# nanoDAP.net
KiCad netlist of a schematic drawn in Altium Designer
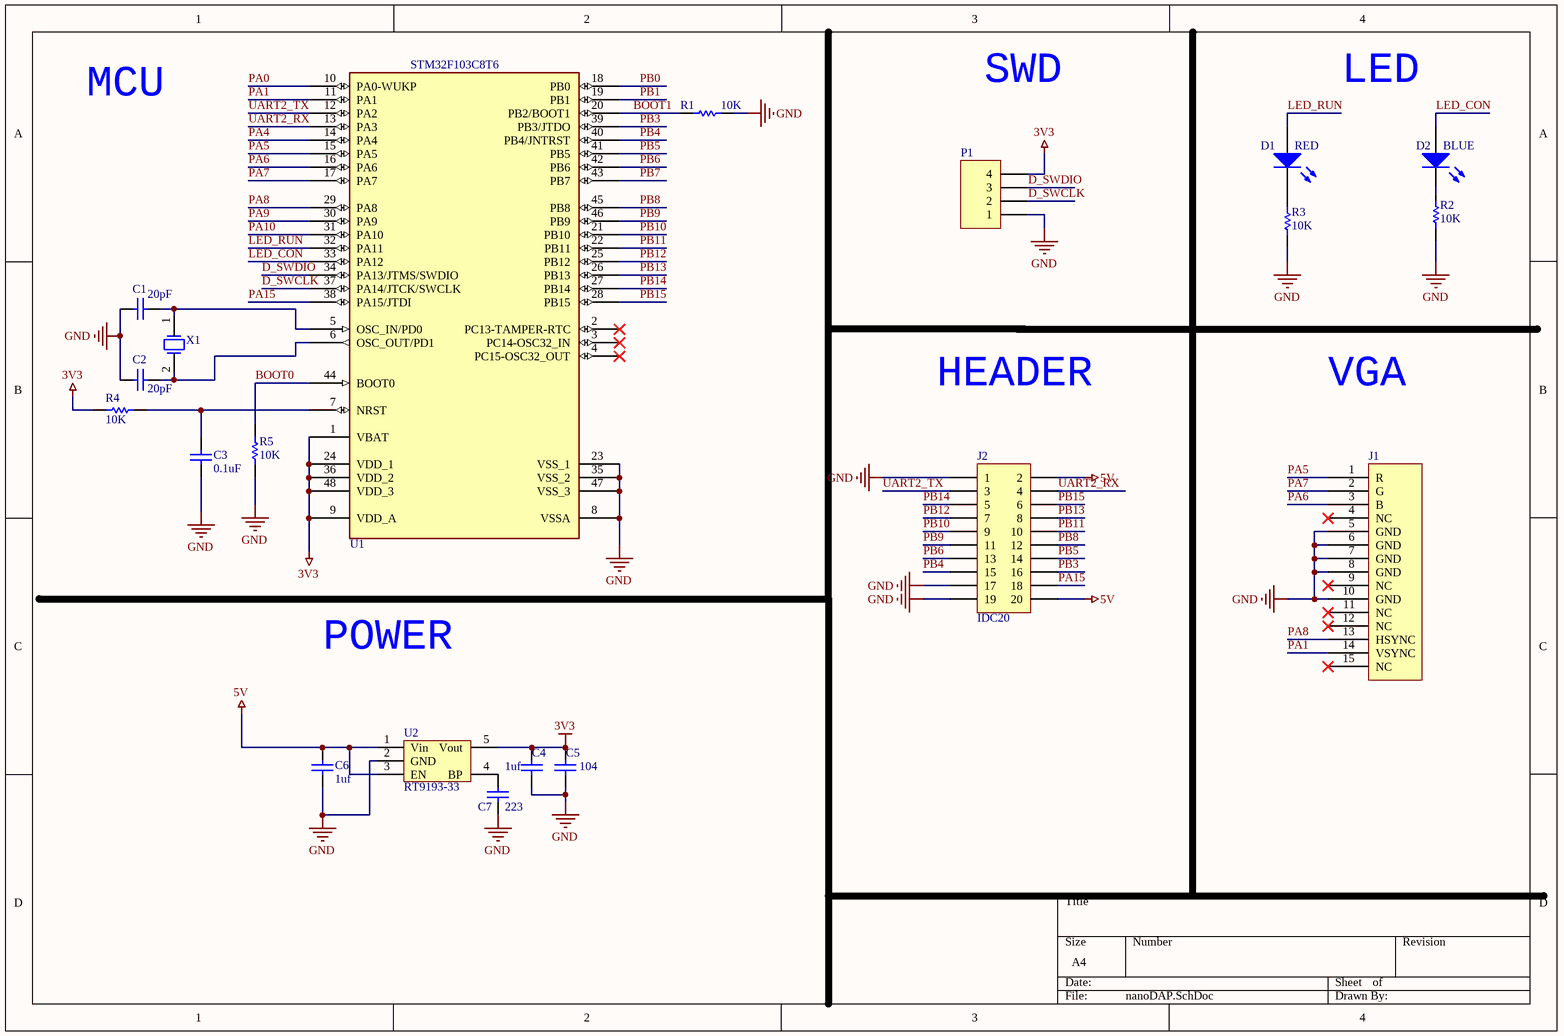
[diagram p0: nanoDAP.SchDoc]

(export (version "E")
  (design (tool "Eeschema 10.0.6"))
  (components
    (comp (ref "C1")
      (value "20pF")
      (footprint "0603_C")
      (description "Capacitor")
      (fields (field (name "Comment") "C0603") (field (name "PUBLISHER") "Altium Limited"))
      (libsource (lib "MYLIB") (part "C-RAD-0603"))
    )
    (comp (ref "C2")
      (value "20pF")
      (footprint "0603_C")
      (description "Capacitor")
      (fields (field (name "Comment") "C0603") (field (name "PUBLISHER") "Altium Limited"))
      (libsource (lib "MYLIB") (part "C-RAD-0603"))
    )
    (comp (ref "C3")
      (value "0.1uF")
      (footprint "0603_C")
      (description "Capacitor")
      (fields (field (name "Comment") "C0603") (field (name "PUBLISHER") "Altium Limited"))
      (libsource (lib "MYLIB") (part "C-RAD-0603"))
    )
    (comp (ref "C4")
      (value "1uf")
      (footprint "0603_C")
      (description "Capacitor")
      (libsource (lib "Cheetie Integrated Library 2017") (part "CAP"))
    )
    (comp (ref "C5")
      (value "104")
      (footprint "0603_C")
      (description "Capacitor")
      (libsource (lib "Cheetie Integrated Library 2017") (part "CAP"))
    )
    (comp (ref "C6")
      (value "1uf")
      (footprint "0603_C")
      (description "Capacitor")
      (libsource (lib "Cheetie Integrated Library 2017") (part "CAP"))
    )
    (comp (ref "C7")
      (value "223")
      (footprint "0603_C")
      (description "Capacitor")
      (libsource (lib "Cheetie Integrated Library 2017") (part "CAP"))
    )
    (comp (ref "D1")
      (value "RED")
      (footprint "0603_LED")
      (description "Typical RED, GREEN, YELLOW, AMBER GaAs LED")
      (fields (field (name "PUBLISHER") "Altium Limited"))
      (libsource (lib "MYLIB") (part "D0603"))
    )
    (comp (ref "D2")
      (value "BLUE")
      (footprint "0603_LED")
      (description "Typical RED, GREEN, YELLOW, AMBER GaAs LED")
      (fields (field (name "PUBLISHER") "Altium Limited"))
      (libsource (lib "MYLIB") (part "D0603"))
    )
    (comp (ref "J1")
      (value "VGA_FEMALE")
      (footprint "VGA15B")
      (libsource (lib "nanoDAP") (part "VGA_FEMALE"))
    )
    (comp (ref "J2") (value "IDC20") (footprint "IDC20") (libsource (lib "nanoDAP") (part "IDC20")))
    (comp (ref "P1")
      (value "Header 4")
      (footprint "HEADER_4x1")
      (description "Header, 4-Pin")
      (fields (field (name "PUBLISHER") "Altium Limited"))
      (libsource (lib "Miscellaneous Connectors") (part "Header 4"))
    )
    (comp (ref "R1")
      (value "10K")
      (footprint "0603_R")
      (description "Resistor")
      (fields (field (name "Comment") "R0603") (field (name "PUBLISHER") "Altium Limited"))
      (libsource (lib "MYLIB") (part "R0603"))
    )
    (comp (ref "R2")
      (value "10K")
      (footprint "0603_R")
      (description "Resistor")
      (fields (field (name "Comment") "R0603") (field (name "PUBLISHER") "Altium Limited"))
      (libsource (lib "MYLIB") (part "0603-1"))
    )
    (comp (ref "R3")
      (value "10K")
      (footprint "0603_R")
      (description "Resistor")
      (fields (field (name "Comment") "R0603") (field (name "PUBLISHER") "Altium Limited"))
      (libsource (lib "MYLIB") (part "0603-1"))
    )
    (comp (ref "R4")
      (value "10K")
      (footprint "0603_R")
      (description "Resistor")
      (fields (field (name "Comment") "R0603") (field (name "PUBLISHER") "Altium Limited"))
      (libsource (lib "MYLIB") (part "0603-1"))
    )
    (comp (ref "R5")
      (value "10K")
      (footprint "0603_R")
      (description "Resistor")
      (fields (field (name "Comment") "R0603") (field (name "PUBLISHER") "Altium Limited"))
      (libsource (lib "MYLIB") (part "0603-1"))
    )
    (comp (ref "U1")
      (value "STM32F103C8T6")
      (footprint "LQFP48_N")
      (description "LowPower MCU")
      (libsource (lib "MYLIB") (part "STM32F103C8T6"))
    )
    (comp (ref "U2")
      (value "RT9193-33")
      (footprint "SOT23-5")
      (libsource (lib "Cheetie Integrated Library 2017") (part "RT9193-33"))
    )
    (comp (ref "X1") (value "XTAL") (footprint "49SMD") (libsource (lib "MYLIB") (part "XTAL")))
  )
  (nets
    (net (code "1") (name "/BOOT0") (class "Default")
      (node (ref "R5") (pin "1") (pinfunction "1_1") (pintype "passive"))
      (node (ref "U1") (pin "44") (pinfunction "BOOT0_44") (pintype "input"))
    )
    (net (code "2") (name "/BOOT1") (class "Default")
      (node (ref "R1") (pin "2") (pinfunction "2_2") (pintype "passive"))
      (node (ref "U1") (pin "20") (pinfunction "PB2/BOOT1_20") (pintype "bidirectional"))
    )
    (net (code "3") (name "/D_SWCLK") (class "Default")
      (node (ref "P1") (pin "2") (pinfunction "2_2") (pintype "passive"))
      (node (ref "U1") (pin "37") (pinfunction "PA14/JTCK/SWCLK_37") (pintype "bidirectional"))
    )
    (net (code "4") (name "/D_SWDIO") (class "Default")
      (node (ref "P1") (pin "3") (pinfunction "3_3") (pintype "passive"))
      (node (ref "U1") (pin "34") (pinfunction "PA13/JTMS/SWDIO_34") (pintype "bidirectional"))
    )
    (net (code "5") (name "/LED_CON") (class "Default")
      (node (ref "D2") (pin "1") (pinfunction "A_1") (pintype "passive"))
      (node (ref "U1") (pin "33") (pinfunction "PA12_33") (pintype "bidirectional"))
    )
    (net (code "6") (name "/LED_RUN") (class "Default")
      (node (ref "D1") (pin "1") (pinfunction "A_1") (pintype "passive"))
      (node (ref "U1") (pin "32") (pinfunction "PA11_32") (pintype "bidirectional"))
    )
    (net (code "7") (name "/PA0") (class "Default")
      (node (ref "U1") (pin "10") (pinfunction "PA0-WUKP_10") (pintype "bidirectional"))
    )
    (net (code "8") (name "/PA1") (class "Default")
      (node (ref "J1") (pin "14") (pinfunction "VSYNC_14") (pintype "passive"))
      (node (ref "U1") (pin "11") (pinfunction "PA1_11") (pintype "bidirectional"))
    )
    (net (code "9") (name "/PA4") (class "Default")
      (node (ref "U1") (pin "14") (pinfunction "PA4_14") (pintype "bidirectional"))
    )
    (net (code "10") (name "/PA5") (class "Default")
      (node (ref "J1") (pin "1") (pinfunction "R_1") (pintype "passive"))
      (node (ref "U1") (pin "15") (pinfunction "PA5_15") (pintype "bidirectional"))
    )
    (net (code "11") (name "/PA6") (class "Default")
      (node (ref "J1") (pin "3") (pinfunction "B_3") (pintype "passive"))
      (node (ref "U1") (pin "16") (pinfunction "PA6_16") (pintype "bidirectional"))
    )
    (net (code "12") (name "/PA7") (class "Default")
      (node (ref "J1") (pin "2") (pinfunction "G_2") (pintype "passive"))
      (node (ref "U1") (pin "17") (pinfunction "PA7_17") (pintype "bidirectional"))
    )
    (net (code "13") (name "/PA8") (class "Default")
      (node (ref "J1") (pin "13") (pinfunction "HSYNC_13") (pintype "passive"))
      (node (ref "U1") (pin "29") (pinfunction "PA8_29") (pintype "bidirectional"))
    )
    (net (code "14") (name "/PA9") (class "Default")
      (node (ref "U1") (pin "30") (pinfunction "PA9_30") (pintype "bidirectional"))
    )
    (net (code "15") (name "/PA10") (class "Default")
      (node (ref "U1") (pin "31") (pinfunction "PA10_31") (pintype "bidirectional"))
    )
    (net (code "16") (name "/PA15") (class "Default")
      (node (ref "J2") (pin "18") (pinfunction "18_18") (pintype "passive"))
      (node (ref "U1") (pin "38") (pinfunction "PA15/JTDI_38") (pintype "bidirectional"))
    )
    (net (code "17") (name "/PB0") (class "Default")
      (node (ref "U1") (pin "18") (pinfunction "PB0_18") (pintype "bidirectional"))
    )
    (net (code "18") (name "/PB1") (class "Default")
      (node (ref "U1") (pin "19") (pinfunction "PB1_19") (pintype "bidirectional"))
    )
    (net (code "19") (name "/PB3") (class "Default")
      (node (ref "J2") (pin "16") (pinfunction "16_16") (pintype "passive"))
      (node (ref "U1") (pin "39") (pinfunction "PB3/JTDO_39") (pintype "bidirectional"))
    )
    (net (code "20") (name "/PB4") (class "Default")
      (node (ref "J2") (pin "15") (pinfunction "15_15") (pintype "passive"))
      (node (ref "U1") (pin "40") (pinfunction "PB4/JNTRST_40") (pintype "bidirectional"))
    )
    (net (code "21") (name "/PB5") (class "Default")
      (node (ref "J2") (pin "14") (pinfunction "14_14") (pintype "passive"))
      (node (ref "U1") (pin "41") (pinfunction "PB5_41") (pintype "bidirectional"))
    )
    (net (code "22") (name "/PB6") (class "Default")
      (node (ref "J2") (pin "13") (pinfunction "13_13") (pintype "passive"))
      (node (ref "U1") (pin "42") (pinfunction "PB6_42") (pintype "bidirectional"))
    )
    (net (code "23") (name "/PB7") (class "Default")
      (node (ref "U1") (pin "43") (pinfunction "PB7_43") (pintype "bidirectional"))
    )
    (net (code "24") (name "/PB8") (class "Default")
      (node (ref "J2") (pin "12") (pinfunction "12_12") (pintype "passive"))
      (node (ref "U1") (pin "45") (pinfunction "PB8_45") (pintype "bidirectional"))
    )
    (net (code "25") (name "/PB9") (class "Default")
      (node (ref "J2") (pin "11") (pinfunction "11_11") (pintype "passive"))
      (node (ref "U1") (pin "46") (pinfunction "PB9_46") (pintype "bidirectional"))
    )
    (net (code "26") (name "/PB10") (class "Default")
      (node (ref "J2") (pin "9") (pinfunction "9_9") (pintype "passive"))
      (node (ref "U1") (pin "21") (pinfunction "PB10_21") (pintype "bidirectional"))
    )
    (net (code "27") (name "/PB11") (class "Default")
      (node (ref "J2") (pin "10") (pinfunction "10_10") (pintype "passive"))
      (node (ref "U1") (pin "22") (pinfunction "PB11_22") (pintype "bidirectional"))
    )
    (net (code "28") (name "/PB12") (class "Default")
      (node (ref "J2") (pin "7") (pinfunction "7_7") (pintype "passive"))
      (node (ref "U1") (pin "25") (pinfunction "PB12_25") (pintype "bidirectional"))
    )
    (net (code "29") (name "/PB13") (class "Default")
      (node (ref "J2") (pin "8") (pinfunction "8_8") (pintype "passive"))
      (node (ref "U1") (pin "26") (pinfunction "PB13_26") (pintype "bidirectional"))
    )
    (net (code "30") (name "/PB14") (class "Default")
      (node (ref "J2") (pin "5") (pinfunction "5_5") (pintype "passive"))
      (node (ref "U1") (pin "27") (pinfunction "PB14_27") (pintype "bidirectional"))
    )
    (net (code "31") (name "/PB15") (class "Default")
      (node (ref "J2") (pin "6") (pinfunction "6_6") (pintype "passive"))
      (node (ref "U1") (pin "28") (pinfunction "PB15_28") (pintype "bidirectional"))
    )
    (net (code "32") (name "/UART2_RX") (class "Default")
      (node (ref "J2") (pin "4") (pinfunction "4_4") (pintype "passive"))
      (node (ref "U1") (pin "13") (pinfunction "PA3_13") (pintype "bidirectional"))
    )
    (net (code "33") (name "/UART2_TX") (class "Default")
      (node (ref "J2") (pin "3") (pinfunction "3_3") (pintype "passive"))
      (node (ref "U1") (pin "12") (pinfunction "PA2_12") (pintype "bidirectional"))
    )
    (net (code "34") (name "3V3") (class "Default")
      (node (ref "C4") (pin "2") (pinfunction "2_2") (pintype "passive"))
      (node (ref "C5") (pin "2") (pinfunction "2_2") (pintype "passive"))
      (node (ref "P1") (pin "4") (pinfunction "4_4") (pintype "passive"))
      (node (ref "R4") (pin "2") (pinfunction "2_2") (pintype "passive"))
      (node (ref "U1") (pin "1") (pinfunction "VBAT_1") (pintype "passive"))
      (node (ref "U1") (pin "24") (pinfunction "VDD_1_24") (pintype "passive"))
      (node (ref "U1") (pin "36") (pinfunction "VDD_2_36") (pintype "passive"))
      (node (ref "U1") (pin "48") (pinfunction "VDD_3_48") (pintype "passive"))
      (node (ref "U1") (pin "9") (pinfunction "VDD_A_9") (pintype "passive"))
      (node (ref "U2") (pin "5") (pinfunction "Vout_5") (pintype "passive"))
    )
    (net (code "35") (name "5V") (class "Default")
      (node (ref "C6") (pin "2") (pinfunction "2_2") (pintype "passive"))
      (node (ref "J2") (pin "2") (pinfunction "2_2") (pintype "passive"))
      (node (ref "J2") (pin "20") (pinfunction "20_20") (pintype "passive"))
      (node (ref "U2") (pin "1") (pinfunction "Vin_1") (pintype "passive"))
      (node (ref "U2") (pin "3") (pinfunction "EN_3") (pintype "passive"))
    )
    (net (code "36") (name "GND") (class "Default")
      (node (ref "C1") (pin "2") (pinfunction "2_2") (pintype "passive"))
      (node (ref "C2") (pin "2") (pinfunction "2_2") (pintype "passive"))
      (node (ref "C3") (pin "1") (pinfunction "1_1") (pintype "passive"))
      (node (ref "C4") (pin "1") (pinfunction "1_1") (pintype "passive"))
      (node (ref "C5") (pin "1") (pinfunction "1_1") (pintype "passive"))
      (node (ref "C6") (pin "1") (pinfunction "1_1") (pintype "passive"))
      (node (ref "C7") (pin "1") (pinfunction "1_1") (pintype "passive"))
      (node (ref "J1") (pin "10") (pinfunction "GND_10") (pintype "passive"))
      (node (ref "J1") (pin "5") (pinfunction "GND_5") (pintype "passive"))
      (node (ref "J1") (pin "6") (pinfunction "GND_6") (pintype "passive"))
      (node (ref "J1") (pin "7") (pinfunction "GND_7") (pintype "passive"))
      (node (ref "J1") (pin "8") (pinfunction "GND_8") (pintype "passive"))
      (node (ref "J2") (pin "1") (pinfunction "1_1") (pintype "passive"))
      (node (ref "J2") (pin "17") (pinfunction "17_17") (pintype "passive"))
      (node (ref "J2") (pin "19") (pinfunction "19_19") (pintype "passive"))
      (node (ref "P1") (pin "1") (pinfunction "1_1") (pintype "passive"))
      (node (ref "R1") (pin "1") (pinfunction "1_1") (pintype "passive"))
      (node (ref "R2") (pin "1") (pinfunction "1_1") (pintype "passive"))
      (node (ref "R3") (pin "1") (pinfunction "1_1") (pintype "passive"))
      (node (ref "R5") (pin "2") (pinfunction "2_2") (pintype "passive"))
      (node (ref "U1") (pin "23") (pinfunction "VSS_1_23") (pintype "passive"))
      (node (ref "U1") (pin "35") (pinfunction "VSS_2_35") (pintype "passive"))
      (node (ref "U1") (pin "47") (pinfunction "VSS_3_47") (pintype "passive"))
      (node (ref "U1") (pin "8") (pinfunction "VSSA_8") (pintype "passive"))
      (node (ref "U2") (pin "2") (pinfunction "GND_2") (pintype "passive"))
    )
    (net (code "37") (name "Net-(D1-K)") (class "Default")
      (node (ref "D1") (pin "2") (pinfunction "K_2") (pintype "passive"))
      (node (ref "R3") (pin "2") (pinfunction "2_2") (pintype "passive"))
    )
    (net (code "38") (name "Net-(D2-K)") (class "Default")
      (node (ref "D2") (pin "2") (pinfunction "K_2") (pintype "passive"))
      (node (ref "R2") (pin "2") (pinfunction "2_2") (pintype "passive"))
    )
    (net (code "39") (name "Net-(U1-NRST)") (class "Default")
      (node (ref "C3") (pin "2") (pinfunction "2_2") (pintype "passive"))
      (node (ref "R4") (pin "1") (pinfunction "1_1") (pintype "passive"))
      (node (ref "U1") (pin "7") (pinfunction "NRST_7") (pintype "bidirectional"))
    )
    (net (code "40") (name "Net-(U1-OSC_IN{slash}PD0)") (class "Default")
      (node (ref "C1") (pin "1") (pinfunction "1_1") (pintype "passive"))
      (node (ref "U1") (pin "5") (pinfunction "OSC_IN/PD0_5") (pintype "input"))
      (node (ref "X1") (pin "1") (pinfunction "1_1") (pintype "passive"))
    )
    (net (code "41") (name "Net-(U1-OSC_OUT{slash}PD1)") (class "Default")
      (node (ref "C2") (pin "1") (pinfunction "1_1") (pintype "passive"))
      (node (ref "U1") (pin "6") (pinfunction "OSC_OUT/PD1_6") (pintype "output"))
      (node (ref "X1") (pin "2") (pinfunction "2_2") (pintype "passive"))
    )
    (net (code "42") (name "Net-(U2-BP)") (class "Default")
      (node (ref "C7") (pin "2") (pinfunction "2_2") (pintype "passive"))
      (node (ref "U2") (pin "4") (pinfunction "BP_4") (pintype "passive"))
    )
    (net (code "43") (name "unconnected-(J1-NC-Pad4)") (class "Default")
      (node (ref "J1") (pin "4") (pinfunction "NC_4") (pintype "passive+no_connect"))
    )
    (net (code "44") (name "unconnected-(J1-NC-Pad9)") (class "Default")
      (node (ref "J1") (pin "9") (pinfunction "NC_9") (pintype "passive+no_connect"))
    )
    (net (code "45") (name "unconnected-(J1-NC-Pad11)") (class "Default")
      (node (ref "J1") (pin "11") (pinfunction "NC_11") (pintype "passive+no_connect"))
    )
    (net (code "46") (name "unconnected-(J1-NC-Pad12)") (class "Default")
      (node (ref "J1") (pin "12") (pinfunction "NC_12") (pintype "passive+no_connect"))
    )
    (net (code "47") (name "unconnected-(J1-NC-Pad15)") (class "Default")
      (node (ref "J1") (pin "15") (pinfunction "NC_15") (pintype "passive+no_connect"))
    )
    (net (code "48") (name "unconnected-(U1-PC13-TAMPER-RTC-Pad2)") (class "Default")
      (node (ref "U1") (pin "2") (pinfunction "PC13-TAMPER-RTC_2") (pintype "bidirectional+no_connect"))
    )
    (net (code "49") (name "unconnected-(U1-PC14-OSC32_IN-Pad3)") (class "Default")
      (node (ref "U1") (pin "3") (pinfunction "PC14-OSC32_IN_3") (pintype "bidirectional+no_connect"))
    )
    (net (code "50") (name "unconnected-(U1-PC15-OSC32_OUT-Pad4)") (class "Default")
      (node (ref "U1") (pin "4") (pinfunction "PC15-OSC32_OUT_4") (pintype "bidirectional+no_connect"))
    )
  )
)
